# board.net
KiCad netlist of a schematic drawn in EAGLE
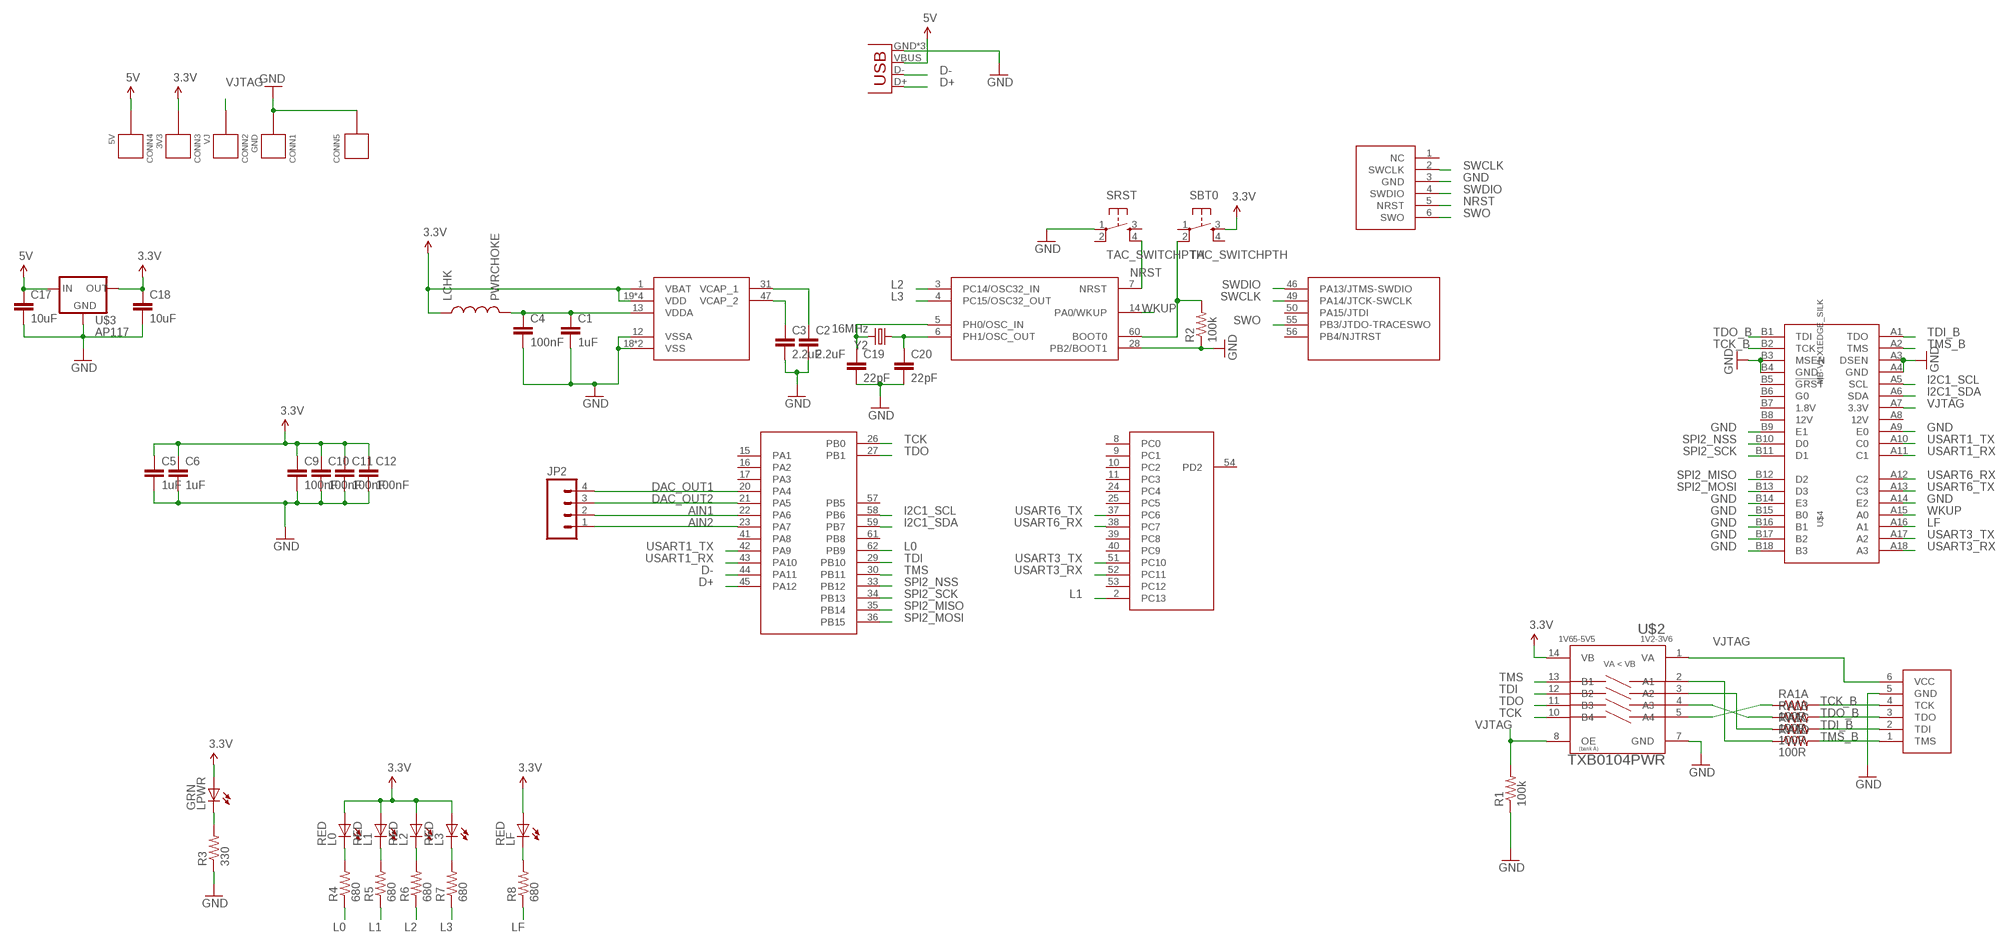
[diagram p0: schematic, sheet 1]

(export (version "E")
  (design (tool "Eeschema 10.0.6"))
  (components
    (comp (ref "C1")
      (value "1uF")
      (footprint "eagle-import:0603-CAP")
      (libsource (lib "eagle-import") (part "CAP0603"))
    )
    (comp (ref "C2")
      (value "2.2uF")
      (footprint "eagle-import:0603-CAP")
      (libsource (lib "eagle-import") (part "CAP0603"))
    )
    (comp (ref "C3")
      (value "2.2uF")
      (footprint "eagle-import:0603-CAP")
      (libsource (lib "eagle-import") (part "CAP0603"))
    )
    (comp (ref "C4")
      (value "100nF")
      (footprint "eagle-import:0402-CAP")
      (libsource (lib "eagle-import") (part "CAP0402-CAP"))
    )
    (comp (ref "C5")
      (value "1uF")
      (footprint "eagle-import:0603-CAP")
      (libsource (lib "eagle-import") (part "CAP0603"))
    )
    (comp (ref "C6")
      (value "1uF")
      (footprint "eagle-import:0603-CAP")
      (libsource (lib "eagle-import") (part "CAP0603"))
    )
    (comp (ref "C9")
      (value "100nF")
      (footprint "eagle-import:0402-CAP")
      (libsource (lib "eagle-import") (part "CAP0402-CAP"))
    )
    (comp (ref "C10")
      (value "100nF")
      (footprint "eagle-import:0402-CAP")
      (libsource (lib "eagle-import") (part "CAP0402-CAP"))
    )
    (comp (ref "C11")
      (value "100nF")
      (footprint "eagle-import:0402-CAP")
      (libsource (lib "eagle-import") (part "CAP0402-CAP"))
    )
    (comp (ref "C12")
      (value "100nF")
      (footprint "eagle-import:0402-CAP")
      (libsource (lib "eagle-import") (part "CAP0402-CAP"))
    )
    (comp (ref "C17")
      (value "10uF")
      (footprint "eagle-import:0805")
      (libsource (lib "eagle-import") (part "CAP0805"))
    )
    (comp (ref "C18")
      (value "10uF")
      (footprint "eagle-import:0805")
      (libsource (lib "eagle-import") (part "CAP0805"))
    )
    (comp (ref "C19")
      (value "22pF")
      (footprint "eagle-import:0402-CAP")
      (libsource (lib "eagle-import") (part "CAP0402-CAP"))
    )
    (comp (ref "C20")
      (value "22pF")
      (footprint "eagle-import:0402-CAP")
      (libsource (lib "eagle-import") (part "CAP0402-CAP"))
    )
    (comp (ref "CONN1")
      (value "GND")
      (footprint "eagle-import:HOLE_22AWG")
      (libsource (lib "eagle-import") (part "CONNECTOR22AWG"))
    )
    (comp (ref "CONN2")
      (value "VJ")
      (footprint "eagle-import:HOLE_22AWG")
      (libsource (lib "eagle-import") (part "CONNECTOR22AWG"))
    )
    (comp (ref "CONN3")
      (value "3V3")
      (footprint "eagle-import:HOLE_22AWG")
      (libsource (lib "eagle-import") (part "CONNECTOR22AWG"))
    )
    (comp (ref "CONN4")
      (value "5V")
      (footprint "eagle-import:HOLE_22AWG")
      (libsource (lib "eagle-import") (part "CONNECTOR22AWG"))
    )
    (comp (ref "CONN5")
      (value "CONNECTORCLIP")
      (footprint "eagle-import:CLIP-AREA")
      (libsource (lib "eagle-import") (part "CONNECTORCLIP"))
    )
    (comp (ref "JP1")
      (value "USB-MICROB")
      (footprint "eagle-import:USB-MICROB")
      (libsource (lib "eagle-import") (part "USB-MICROB"))
    )
    (comp (ref "JP2")
      (value "M04PTH")
      (footprint "eagle-import:1X04")
      (libsource (lib "eagle-import") (part "M04PTH"))
    )
    (comp (ref "L0")
      (value "RED")
      (footprint "eagle-import:0603_LED")
      (libsource (lib "eagle-import") (part "LED0603"))
    )
    (comp (ref "L1")
      (value "RED")
      (footprint "eagle-import:0603_LED")
      (libsource (lib "eagle-import") (part "LED0603"))
    )
    (comp (ref "L2")
      (value "RED")
      (footprint "eagle-import:0603_LED")
      (libsource (lib "eagle-import") (part "LED0603"))
    )
    (comp (ref "L3")
      (value "RED")
      (footprint "eagle-import:0603_LED")
      (libsource (lib "eagle-import") (part "LED0603"))
    )
    (comp (ref "LCHK")
      (value "PWRCHOKE")
      (footprint "eagle-import:0603")
      (libsource (lib "eagle-import") (part "INDUCTOR0603"))
    )
    (comp (ref "LF")
      (value "RED")
      (footprint "eagle-import:0603_LED")
      (libsource (lib "eagle-import") (part "LED0603"))
    )
    (comp (ref "LPWR")
      (value "GRN")
      (footprint "eagle-import:0603_LED")
      (libsource (lib "eagle-import") (part "LED0603"))
    )
    (comp (ref "R1")
      (value "100k")
      (footprint "eagle-import:0603-RES")
      (libsource (lib "eagle-import") (part "RESISTOR0603"))
    )
    (comp (ref "R2")
      (value "100k")
      (footprint "eagle-import:0603-RES")
      (libsource (lib "eagle-import") (part "RESISTOR0603"))
    )
    (comp (ref "R3")
      (value "330")
      (footprint "eagle-import:0603-RES")
      (libsource (lib "eagle-import") (part "RESISTOR0603"))
    )
    (comp (ref "R4")
      (value "680")
      (footprint "eagle-import:0603-RES")
      (libsource (lib "eagle-import") (part "RESISTOR0603"))
    )
    (comp (ref "R5")
      (value "680")
      (footprint "eagle-import:0603-RES")
      (libsource (lib "eagle-import") (part "RESISTOR0603"))
    )
    (comp (ref "R6")
      (value "680")
      (footprint "eagle-import:0603-RES")
      (libsource (lib "eagle-import") (part "RESISTOR0603"))
    )
    (comp (ref "R7")
      (value "680")
      (footprint "eagle-import:0603-RES")
      (libsource (lib "eagle-import") (part "RESISTOR0603"))
    )
    (comp (ref "R8")
      (value "680")
      (footprint "eagle-import:0603-RES")
      (libsource (lib "eagle-import") (part "RESISTOR0603"))
    )
    (comp (ref "RA1")
      (value "100R")
      (footprint "eagle-import:0603-ARV")
      (libsource (lib "eagle-import") (part "RESISTOR_ARRAY0603_X4"))
    )
    (comp (ref "SBT0")
      (value "TAC_SWITCHPTH")
      (footprint "eagle-import:TACTILE-PTH")
      (libsource (lib "eagle-import") (part "TAC_SWITCHPTH"))
    )
    (comp (ref "SRST")
      (value "TAC_SWITCHPTH")
      (footprint "eagle-import:TACTILE-PTH")
      (libsource (lib "eagle-import") (part "TAC_SWITCHPTH"))
    )
    (comp (ref "U$1")
      (value "STM32F407R")
      (footprint "eagle-import:TQFP64_LONGPAD")
      (libsource (lib "eagle-import") (part "STM32F407R"))
    )
    (comp (ref "U$2")
      (value "TXB0104PWR")
      (footprint "eagle-import:TSSOP14")
      (libsource (lib "eagle-import") (part "TXB0104PWR"))
    )
    (comp (ref "U$3")
      (value "AP117")
      (footprint "eagle-import:SOT223")
      (libsource (lib "eagle-import") (part "VREGSOT223"))
    )
    (comp (ref "U$4")
      (value "MB-V1-X1EDGE_SILK")
      (footprint "eagle-import:MB-V1-X1-EDGE")
      (libsource (lib "eagle-import") (part "MB-V1-X1EDGE_SILK"))
    )
    (comp (ref "U$5")
      (value "JTAGDIGILENT")
      (footprint "eagle-import:1X06")
      (libsource (lib "eagle-import") (part "JTAGDIGILENT"))
    )
    (comp (ref "U$6")
      (value "STLINK")
      (footprint "eagle-import:1X06")
      (libsource (lib "eagle-import") (part "STLINK"))
    )
    (comp (ref "Y2")
      (value "16MHz")
      (footprint "eagle-import:HC49US")
      (libsource (lib "eagle-import") (part "CRYSTALHC49US"))
    )
  )
  (nets
    (net (code "1") (name "/AIN1") (class "Default")
      (node (ref "JP2") (pin "2") (pinfunction "2_2") (pintype "passive"))
      (node (ref "U$1") (pin "22") (pinfunction "PA6_22") (pintype "bidirectional"))
    )
    (net (code "2") (name "/AIN2") (class "Default")
      (node (ref "JP2") (pin "1") (pinfunction "1_1") (pintype "passive"))
      (node (ref "U$1") (pin "23") (pinfunction "PA7_23") (pintype "bidirectional"))
    )
    (net (code "3") (name "/D+") (class "Default")
      (node (ref "JP1") (pin "D+") (pinfunction "D+_D+") (pintype "bidirectional"))
      (node (ref "U$1") (pin "45") (pinfunction "PA12_45") (pintype "bidirectional"))
    )
    (net (code "4") (name "/D-") (class "Default")
      (node (ref "JP1") (pin "D-") (pinfunction "D-_D-") (pintype "bidirectional"))
      (node (ref "U$1") (pin "44") (pinfunction "PA11_44") (pintype "bidirectional"))
    )
    (net (code "5") (name "/DAC_OUT1") (class "Default")
      (node (ref "JP2") (pin "4") (pinfunction "4_4") (pintype "passive"))
      (node (ref "U$1") (pin "20") (pinfunction "PA4_20") (pintype "bidirectional"))
    )
    (net (code "6") (name "/DAC_OUT2") (class "Default")
      (node (ref "JP2") (pin "3") (pinfunction "3_3") (pintype "passive"))
      (node (ref "U$1") (pin "21") (pinfunction "PA5_21") (pintype "bidirectional"))
    )
    (net (code "7") (name "/I2C1_SCL") (class "Default")
      (node (ref "U$1") (pin "58") (pinfunction "PB6_58") (pintype "bidirectional"))
      (node (ref "U$4") (pin "A5") (pinfunction "SCL_A5") (pintype "bidirectional"))
    )
    (net (code "8") (name "/I2C1_SDA") (class "Default")
      (node (ref "U$1") (pin "59") (pinfunction "PB7_59") (pintype "bidirectional"))
      (node (ref "U$4") (pin "A6") (pinfunction "SDA_A6") (pintype "bidirectional"))
    )
    (net (code "9") (name "/L0") (class "Default")
      (node (ref "R4") (pin "1") (pinfunction "1_1") (pintype "passive"))
      (node (ref "U$1") (pin "62") (pinfunction "PB9_62") (pintype "bidirectional"))
    )
    (net (code "10") (name "/L1") (class "Default")
      (node (ref "R5") (pin "1") (pinfunction "1_1") (pintype "passive"))
      (node (ref "U$1") (pin "2") (pinfunction "PC13_2") (pintype "bidirectional"))
    )
    (net (code "11") (name "/L2") (class "Default")
      (node (ref "R6") (pin "1") (pinfunction "1_1") (pintype "passive"))
      (node (ref "U$1") (pin "3") (pinfunction "PC14/OSC32_IN_3") (pintype "bidirectional"))
    )
    (net (code "12") (name "/L3") (class "Default")
      (node (ref "R7") (pin "1") (pinfunction "1_1") (pintype "passive"))
      (node (ref "U$1") (pin "4") (pinfunction "PC15/OSC32_OUT_4") (pintype "bidirectional"))
    )
    (net (code "13") (name "/LF") (class "Default")
      (node (ref "R8") (pin "1") (pinfunction "1_1") (pintype "passive"))
      (node (ref "U$4") (pin "A16") (pinfunction "A1_A16") (pintype "bidirectional"))
    )
    (net (code "14") (name "/NRST") (class "Default")
      (node (ref "SRST") (pin "4") (pinfunction "4_4") (pintype "passive"))
      (node (ref "U$1") (pin "7") (pinfunction "NRST_7") (pintype "input"))
      (node (ref "U$6") (pin "5") (pinfunction "NRST_5") (pintype "bidirectional"))
    )
    (net (code "15") (name "/SPI2_MISO") (class "Default")
      (node (ref "U$1") (pin "35") (pinfunction "PB14_35") (pintype "bidirectional"))
      (node (ref "U$4") (pin "B12") (pinfunction "D2_B12") (pintype "bidirectional"))
    )
    (net (code "16") (name "/SPI2_MOSI") (class "Default")
      (node (ref "U$1") (pin "36") (pinfunction "PB15_36") (pintype "bidirectional"))
      (node (ref "U$4") (pin "B13") (pinfunction "D3_B13") (pintype "bidirectional"))
    )
    (net (code "17") (name "/SPI2_NSS") (class "Default")
      (node (ref "U$1") (pin "33") (pinfunction "PB12_33") (pintype "bidirectional"))
      (node (ref "U$4") (pin "B10") (pinfunction "D0_B10") (pintype "bidirectional"))
    )
    (net (code "18") (name "/SPI2_SCK") (class "Default")
      (node (ref "U$1") (pin "34") (pinfunction "PB13_34") (pintype "bidirectional"))
      (node (ref "U$4") (pin "B11") (pinfunction "D1_B11") (pintype "bidirectional"))
    )
    (net (code "19") (name "/SWCLK") (class "Default")
      (node (ref "U$1") (pin "49") (pinfunction "PA14/JTCK-SWCLK_49") (pintype "bidirectional"))
      (node (ref "U$6") (pin "2") (pinfunction "SWCLK_2") (pintype "bidirectional"))
    )
    (net (code "20") (name "/SWDIO") (class "Default")
      (node (ref "U$1") (pin "46") (pinfunction "PA13/JTMS-SWDIO_46") (pintype "bidirectional"))
      (node (ref "U$6") (pin "4") (pinfunction "SWDIO_4") (pintype "bidirectional"))
    )
    (net (code "21") (name "/SWO") (class "Default")
      (node (ref "U$1") (pin "55") (pinfunction "PB3/JTDO-TRACESWO_55") (pintype "bidirectional"))
      (node (ref "U$6") (pin "6") (pinfunction "SWO_6") (pintype "bidirectional"))
    )
    (net (code "22") (name "/TCK") (class "Default")
      (node (ref "U$1") (pin "26") (pinfunction "PB0_26") (pintype "bidirectional"))
      (node (ref "U$2") (pin "10") (pinfunction "B4_10") (pintype "bidirectional"))
    )
    (net (code "23") (name "/TCK_B") (class "Default")
      (node (ref "RA1") (pin "8") (pinfunction "2_8") (pintype "passive"))
      (node (ref "U$4") (pin "B2") (pinfunction "TCK_B2") (pintype "bidirectional"))
      (node (ref "U$5") (pin "4") (pinfunction "TCK_4") (pintype "bidirectional"))
    )
    (net (code "24") (name "/TDI") (class "Default")
      (node (ref "U$1") (pin "29") (pinfunction "PB10_29") (pintype "bidirectional"))
      (node (ref "U$2") (pin "12") (pinfunction "B2_12") (pintype "bidirectional"))
    )
    (net (code "25") (name "/TDI_B") (class "Default")
      (node (ref "RA1") (pin "6") (pinfunction "2_6") (pintype "passive"))
      (node (ref "U$4") (pin "A1") (pinfunction "TDO_A1") (pintype "bidirectional"))
      (node (ref "U$5") (pin "2") (pinfunction "TDI_2") (pintype "bidirectional"))
    )
    (net (code "26") (name "/TDO") (class "Default")
      (node (ref "U$1") (pin "27") (pinfunction "PB1_27") (pintype "bidirectional"))
      (node (ref "U$2") (pin "11") (pinfunction "B3_11") (pintype "bidirectional"))
    )
    (net (code "27") (name "/TDO_B") (class "Default")
      (node (ref "RA1") (pin "7") (pinfunction "2_7") (pintype "passive"))
      (node (ref "U$4") (pin "B1") (pinfunction "TDI_B1") (pintype "bidirectional"))
      (node (ref "U$5") (pin "3") (pinfunction "TDO_3") (pintype "bidirectional"))
    )
    (net (code "28") (name "/TMS") (class "Default")
      (node (ref "U$1") (pin "30") (pinfunction "PB11_30") (pintype "bidirectional"))
      (node (ref "U$2") (pin "13") (pinfunction "B1_13") (pintype "bidirectional"))
    )
    (net (code "29") (name "/TMS_B") (class "Default")
      (node (ref "RA1") (pin "5") (pinfunction "2_5") (pintype "passive"))
      (node (ref "U$4") (pin "A2") (pinfunction "TMS_A2") (pintype "bidirectional"))
      (node (ref "U$5") (pin "1") (pinfunction "TMS_1") (pintype "bidirectional"))
    )
    (net (code "30") (name "/USART1_RX") (class "Default")
      (node (ref "U$1") (pin "43") (pinfunction "PA10_43") (pintype "bidirectional"))
      (node (ref "U$4") (pin "A11") (pinfunction "C1_A11") (pintype "bidirectional"))
    )
    (net (code "31") (name "/USART1_TX") (class "Default")
      (node (ref "U$1") (pin "42") (pinfunction "PA9_42") (pintype "bidirectional"))
      (node (ref "U$4") (pin "A10") (pinfunction "C0_A10") (pintype "bidirectional"))
    )
    (net (code "32") (name "/USART3_RX") (class "Default")
      (node (ref "U$1") (pin "52") (pinfunction "PC11_52") (pintype "bidirectional"))
      (node (ref "U$4") (pin "A18") (pinfunction "A3_A18") (pintype "bidirectional"))
    )
    (net (code "33") (name "/USART3_TX") (class "Default")
      (node (ref "U$1") (pin "51") (pinfunction "PC10_51") (pintype "bidirectional"))
      (node (ref "U$4") (pin "A17") (pinfunction "A2_A17") (pintype "bidirectional"))
    )
    (net (code "34") (name "/USART6_RX") (class "Default")
      (node (ref "U$1") (pin "38") (pinfunction "PC7_38") (pintype "bidirectional"))
      (node (ref "U$4") (pin "A12") (pinfunction "C2_A12") (pintype "bidirectional"))
    )
    (net (code "35") (name "/USART6_TX") (class "Default")
      (node (ref "U$1") (pin "37") (pinfunction "PC6_37") (pintype "bidirectional"))
      (node (ref "U$4") (pin "A13") (pinfunction "C3_A13") (pintype "bidirectional"))
    )
    (net (code "36") (name "/VJTAG") (class "Default")
      (node (ref "CONN2") (pin "P") (pinfunction "P_P") (pintype "bidirectional"))
      (node (ref "R1") (pin "2") (pinfunction "2_2") (pintype "passive"))
      (node (ref "U$2") (pin "1") (pinfunction "VA_1") (pintype "bidirectional"))
      (node (ref "U$2") (pin "8") (pinfunction "OE_8") (pintype "bidirectional"))
      (node (ref "U$4") (pin "A7") (pinfunction "3.3V_A7") (pintype "bidirectional"))
      (node (ref "U$5") (pin "6") (pinfunction "VCC_6") (pintype "bidirectional"))
    )
    (net (code "37") (name "/WKUP") (class "Default")
      (node (ref "U$1") (pin "14") (pinfunction "PA0/WKUP_14") (pintype "input"))
      (node (ref "U$4") (pin "A15") (pinfunction "A0_A15") (pintype "bidirectional"))
    )
    (net (code "38") (name "3.3V") (class "Default")
      (node (ref "C10") (pin "1") (pinfunction "1_1") (pintype "passive"))
      (node (ref "C11") (pin "1") (pinfunction "1_1") (pintype "passive"))
      (node (ref "C12") (pin "1") (pinfunction "1_1") (pintype "passive"))
      (node (ref "C18") (pin "1") (pinfunction "1_1") (pintype "passive"))
      (node (ref "C5") (pin "1") (pinfunction "1_1") (pintype "passive"))
      (node (ref "C6") (pin "1") (pinfunction "1_1") (pintype "passive"))
      (node (ref "C9") (pin "1") (pinfunction "1_1") (pintype "passive"))
      (node (ref "CONN3") (pin "P") (pinfunction "P_P") (pintype "bidirectional"))
      (node (ref "L0") (pin "A") (pinfunction "A_A") (pintype "passive"))
      (node (ref "L1") (pin "A") (pinfunction "A_A") (pintype "passive"))
      (node (ref "L2") (pin "A") (pinfunction "A_A") (pintype "passive"))
      (node (ref "L3") (pin "A") (pinfunction "A_A") (pintype "passive"))
      (node (ref "LCHK") (pin "1") (pinfunction "1_1") (pintype "passive"))
      (node (ref "LF") (pin "A") (pinfunction "A_A") (pintype "passive"))
      (node (ref "LPWR") (pin "A") (pinfunction "A_A") (pintype "passive"))
      (node (ref "SBT0") (pin "3") (pinfunction "3_3") (pintype "passive"))
      (node (ref "U$1") (pin "1") (pinfunction "VBAT_1") (pintype "input"))
      (node (ref "U$1") (pin "19") (pinfunction "VDD_19") (pintype "input"))
      (node (ref "U$1") (pin "32") (pinfunction "VDD_32") (pintype "input"))
      (node (ref "U$1") (pin "48") (pinfunction "VDD_48") (pintype "input"))
      (node (ref "U$1") (pin "64") (pinfunction "VDD_64") (pintype "input"))
      (node (ref "U$2") (pin "14") (pinfunction "VB_14") (pintype "bidirectional"))
      (node (ref "U$3") (pin "2") (pinfunction "OUT_2") (pintype "passive"))
      (node (ref "U$3") (pin "4") (pinfunction "OUT_4") (pintype "passive"))
    )
    (net (code "39") (name "5V") (class "Default")
      (node (ref "C17") (pin "1") (pinfunction "1_1") (pintype "passive"))
      (node (ref "CONN4") (pin "P") (pinfunction "P_P") (pintype "bidirectional"))
      (node (ref "JP1") (pin "VBUS") (pinfunction "VBUS_VBUS") (pintype "bidirectional"))
      (node (ref "U$3") (pin "3") (pinfunction "IN_3") (pintype "input"))
    )
    (net (code "40") (name "GND") (class "Default")
      (node (ref "C1") (pin "2") (pinfunction "2_2") (pintype "passive"))
      (node (ref "C10") (pin "2") (pinfunction "2_2") (pintype "passive"))
      (node (ref "C11") (pin "2") (pinfunction "2_2") (pintype "passive"))
      (node (ref "C12") (pin "2") (pinfunction "2_2") (pintype "passive"))
      (node (ref "C17") (pin "2") (pinfunction "2_2") (pintype "passive"))
      (node (ref "C18") (pin "2") (pinfunction "2_2") (pintype "passive"))
      (node (ref "C19") (pin "2") (pinfunction "2_2") (pintype "passive"))
      (node (ref "C2") (pin "2") (pinfunction "2_2") (pintype "passive"))
      (node (ref "C20") (pin "2") (pinfunction "2_2") (pintype "passive"))
      (node (ref "C3") (pin "2") (pinfunction "2_2") (pintype "passive"))
      (node (ref "C4") (pin "2") (pinfunction "2_2") (pintype "passive"))
      (node (ref "C5") (pin "2") (pinfunction "2_2") (pintype "passive"))
      (node (ref "C6") (pin "2") (pinfunction "2_2") (pintype "passive"))
      (node (ref "C9") (pin "2") (pinfunction "2_2") (pintype "passive"))
      (node (ref "CONN1") (pin "P") (pinfunction "P_P") (pintype "bidirectional"))
      (node (ref "CONN5") (pin "P$1") (pinfunction "P_P$1") (pintype "bidirectional"))
      (node (ref "CONN5") (pin "P$2") (pinfunction "P_P$2") (pintype "bidirectional"))
      (node (ref "JP1") (pin "GND") (pinfunction "GND_GND") (pintype "bidirectional"))
      (node (ref "JP1") (pin "MT1") (pinfunction "GND_MT1") (pintype "bidirectional"))
      (node (ref "JP1") (pin "MT2") (pinfunction "GND_MT2") (pintype "bidirectional"))
      (node (ref "R1") (pin "1") (pinfunction "1_1") (pintype "passive"))
      (node (ref "R2") (pin "1") (pinfunction "1_1") (pintype "passive"))
      (node (ref "R3") (pin "1") (pinfunction "1_1") (pintype "passive"))
      (node (ref "SRST") (pin "1") (pinfunction "1_1") (pintype "passive"))
      (node (ref "U$1") (pin "12") (pinfunction "VSSA_12") (pintype "input"))
      (node (ref "U$1") (pin "18") (pinfunction "VSS_18") (pintype "input"))
      (node (ref "U$1") (pin "28") (pinfunction "PB2/BOOT1_28") (pintype "input"))
      (node (ref "U$1") (pin "63") (pinfunction "VSS_63") (pintype "input"))
      (node (ref "U$2") (pin "7") (pinfunction "GND_7") (pintype "bidirectional"))
      (node (ref "U$3") (pin "1") (pinfunction "GND_1") (pintype "input"))
      (node (ref "U$4") (pin "A14") (pinfunction "E2_A14") (pintype "bidirectional"))
      (node (ref "U$4") (pin "A3") (pinfunction "DSEN_A3") (pintype "bidirectional"))
      (node (ref "U$4") (pin "A4") (pinfunction "GND_A4") (pintype "bidirectional"))
      (node (ref "U$4") (pin "A9") (pinfunction "E0_A9") (pintype "bidirectional"))
      (node (ref "U$4") (pin "B14") (pinfunction "E3_B14") (pintype "bidirectional"))
      (node (ref "U$4") (pin "B15") (pinfunction "B0_B15") (pintype "bidirectional"))
      (node (ref "U$4") (pin "B16") (pinfunction "B1_B16") (pintype "bidirectional"))
      (node (ref "U$4") (pin "B17") (pinfunction "B2_B17") (pintype "bidirectional"))
      (node (ref "U$4") (pin "B18") (pinfunction "B3_B18") (pintype "bidirectional"))
      (node (ref "U$4") (pin "B3") (pinfunction "MSEN_B3") (pintype "bidirectional"))
      (node (ref "U$4") (pin "B4") (pinfunction "GND_B4") (pintype "bidirectional"))
      (node (ref "U$4") (pin "B9") (pinfunction "E1_B9") (pintype "bidirectional"))
      (node (ref "U$5") (pin "5") (pinfunction "GND_5") (pintype "bidirectional"))
      (node (ref "U$6") (pin "3") (pinfunction "GND_3") (pintype "bidirectional"))
    )
    (net (code "41") (name "Net-(L0-PadC)") (class "Default")
      (node (ref "L0") (pin "C") (pinfunction "C_C") (pintype "passive"))
      (node (ref "R4") (pin "2") (pinfunction "2_2") (pintype "passive"))
    )
    (net (code "42") (name "Net-(L1-PadC)") (class "Default")
      (node (ref "L1") (pin "C") (pinfunction "C_C") (pintype "passive"))
      (node (ref "R5") (pin "2") (pinfunction "2_2") (pintype "passive"))
    )
    (net (code "43") (name "Net-(L2-PadC)") (class "Default")
      (node (ref "L2") (pin "C") (pinfunction "C_C") (pintype "passive"))
      (node (ref "R6") (pin "2") (pinfunction "2_2") (pintype "passive"))
    )
    (net (code "44") (name "Net-(L3-PadC)") (class "Default")
      (node (ref "L3") (pin "C") (pinfunction "C_C") (pintype "passive"))
      (node (ref "R7") (pin "2") (pinfunction "2_2") (pintype "passive"))
    )
    (net (code "45") (name "Net-(LF-PadC)") (class "Default")
      (node (ref "LF") (pin "C") (pinfunction "C_C") (pintype "passive"))
      (node (ref "R8") (pin "2") (pinfunction "2_2") (pintype "passive"))
    )
    (net (code "46") (name "Net-(LPWR-PadC)") (class "Default")
      (node (ref "LPWR") (pin "C") (pinfunction "C_C") (pintype "passive"))
      (node (ref "R3") (pin "2") (pinfunction "2_2") (pintype "passive"))
    )
    (net (code "47") (name "Net-(RA1B-1)") (class "Default")
      (node (ref "RA1") (pin "2") (pinfunction "1_2") (pintype "passive"))
      (node (ref "U$2") (pin "4") (pinfunction "A3_4") (pintype "bidirectional"))
    )
    (net (code "48") (name "Net-(RA1C-1)") (class "Default")
      (node (ref "RA1") (pin "3") (pinfunction "1_3") (pintype "passive"))
      (node (ref "U$2") (pin "3") (pinfunction "A2_3") (pintype "bidirectional"))
    )
    (net (code "49") (name "Net-(RA1D-1)") (class "Default")
      (node (ref "RA1") (pin "4") (pinfunction "1_4") (pintype "passive"))
      (node (ref "U$2") (pin "2") (pinfunction "A1_2") (pintype "bidirectional"))
    )
    (net (code "50") (name "Net-(U$1-BOOT0)") (class "Default")
      (node (ref "R2") (pin "2") (pinfunction "2_2") (pintype "passive"))
      (node (ref "SBT0") (pin "2") (pinfunction "2_2") (pintype "passive"))
      (node (ref "U$1") (pin "60") (pinfunction "BOOT0_60") (pintype "input"))
    )
    (net (code "51") (name "Net-(U$1-PH0{slash}OSC_IN)") (class "Default")
      (node (ref "C19") (pin "1") (pinfunction "1_1") (pintype "passive"))
      (node (ref "U$1") (pin "5") (pinfunction "PH0/OSC_IN_5") (pintype "bidirectional"))
      (node (ref "Y2") (pin "2") (pinfunction "2_2") (pintype "passive"))
    )
    (net (code "52") (name "Net-(U$1-PH1{slash}OSC_OUT)") (class "Default")
      (node (ref "C20") (pin "1") (pinfunction "1_1") (pintype "passive"))
      (node (ref "U$1") (pin "6") (pinfunction "PH1/OSC_OUT_6") (pintype "bidirectional"))
      (node (ref "Y2") (pin "1") (pinfunction "1_1") (pintype "passive"))
    )
    (net (code "53") (name "Net-(U$1-VCAP_1)") (class "Default")
      (node (ref "C2") (pin "1") (pinfunction "1_1") (pintype "passive"))
      (node (ref "U$1") (pin "31") (pinfunction "VCAP_1_31") (pintype "input"))
    )
    (net (code "54") (name "Net-(U$1-VCAP_2)") (class "Default")
      (node (ref "C3") (pin "1") (pinfunction "1_1") (pintype "passive"))
      (node (ref "U$1") (pin "47") (pinfunction "VCAP_2_47") (pintype "input"))
    )
    (net (code "55") (name "Net-(U$1-VDDA)") (class "Default")
      (node (ref "C1") (pin "1") (pinfunction "1_1") (pintype "passive"))
      (node (ref "C4") (pin "1") (pinfunction "1_1") (pintype "passive"))
      (node (ref "LCHK") (pin "2") (pinfunction "2_2") (pintype "passive"))
      (node (ref "U$1") (pin "13") (pinfunction "VDDA_13") (pintype "input"))
    )
    (net (code "56") (name "Net-(U$2-A4)") (class "Default")
      (node (ref "RA1") (pin "1") (pinfunction "1_1") (pintype "passive"))
      (node (ref "U$2") (pin "5") (pinfunction "A4_5") (pintype "bidirectional"))
    )
    (net (code "57") (name "unconnected-(SBT0-Pad1)") (class "Default")
      (node (ref "SBT0") (pin "1") (pinfunction "1_1") (pintype "passive"))
    )
    (net (code "58") (name "unconnected-(SBT0-Pad4)") (class "Default")
      (node (ref "SBT0") (pin "4") (pinfunction "4_4") (pintype "passive"))
    )
    (net (code "59") (name "unconnected-(SRST-Pad2)") (class "Default")
      (node (ref "SRST") (pin "2") (pinfunction "2_2") (pintype "passive"))
    )
    (net (code "60") (name "unconnected-(SRST-Pad3)") (class "Default")
      (node (ref "SRST") (pin "3") (pinfunction "3_3") (pintype "passive"))
    )
    (net (code "61") (name "unconnected-(U$1-PA1-Pad15)") (class "Default")
      (node (ref "U$1") (pin "15") (pinfunction "PA1_15") (pintype "bidirectional"))
    )
    (net (code "62") (name "unconnected-(U$1-PA2-Pad16)") (class "Default")
      (node (ref "U$1") (pin "16") (pinfunction "PA2_16") (pintype "bidirectional"))
    )
    (net (code "63") (name "unconnected-(U$1-PA3-Pad17)") (class "Default")
      (node (ref "U$1") (pin "17") (pinfunction "PA3_17") (pintype "bidirectional"))
    )
    (net (code "64") (name "unconnected-(U$1-PA8-Pad41)") (class "Default")
      (node (ref "U$1") (pin "41") (pinfunction "PA8_41") (pintype "bidirectional"))
    )
    (net (code "65") (name "unconnected-(U$1-PA15{slash}JTDI-Pad50)") (class "Default")
      (node (ref "U$1") (pin "50") (pinfunction "PA15/JTDI_50") (pintype "bidirectional"))
    )
    (net (code "66") (name "unconnected-(U$1-PB4{slash}NJTRST-Pad56)") (class "Default")
      (node (ref "U$1") (pin "56") (pinfunction "PB4/NJTRST_56") (pintype "bidirectional"))
    )
    (net (code "67") (name "unconnected-(U$1-PB5-Pad57)") (class "Default")
      (node (ref "U$1") (pin "57") (pinfunction "PB5_57") (pintype "bidirectional"))
    )
    (net (code "68") (name "unconnected-(U$1-PB8-Pad61)") (class "Default")
      (node (ref "U$1") (pin "61") (pinfunction "PB8_61") (pintype "bidirectional"))
    )
    (net (code "69") (name "unconnected-(U$1-PC0-Pad8)") (class "Default")
      (node (ref "U$1") (pin "8") (pinfunction "PC0_8") (pintype "bidirectional"))
    )
    (net (code "70") (name "unconnected-(U$1-PC1-Pad9)") (class "Default")
      (node (ref "U$1") (pin "9") (pinfunction "PC1_9") (pintype "bidirectional"))
    )
    (net (code "71") (name "unconnected-(U$1-PC2-Pad10)") (class "Default")
      (node (ref "U$1") (pin "10") (pinfunction "PC2_10") (pintype "bidirectional"))
    )
    (net (code "72") (name "unconnected-(U$1-PC3-Pad11)") (class "Default")
      (node (ref "U$1") (pin "11") (pinfunction "PC3_11") (pintype "bidirectional"))
    )
    (net (code "73") (name "unconnected-(U$1-PC4-Pad24)") (class "Default")
      (node (ref "U$1") (pin "24") (pinfunction "PC4_24") (pintype "bidirectional"))
    )
    (net (code "74") (name "unconnected-(U$1-PC5-Pad25)") (class "Default")
      (node (ref "U$1") (pin "25") (pinfunction "PC5_25") (pintype "bidirectional"))
    )
    (net (code "75") (name "unconnected-(U$1-PC8-Pad39)") (class "Default")
      (node (ref "U$1") (pin "39") (pinfunction "PC8_39") (pintype "bidirectional"))
    )
    (net (code "76") (name "unconnected-(U$1-PC9-Pad40)") (class "Default")
      (node (ref "U$1") (pin "40") (pinfunction "PC9_40") (pintype "bidirectional"))
    )
    (net (code "77") (name "unconnected-(U$1-PC12-Pad53)") (class "Default")
      (node (ref "U$1") (pin "53") (pinfunction "PC12_53") (pintype "bidirectional"))
    )
    (net (code "78") (name "unconnected-(U$1-PD2-Pad54)") (class "Default")
      (node (ref "U$1") (pin "54") (pinfunction "PD2_54") (pintype "bidirectional"))
    )
    (net (code "79") (name "unconnected-(U$4-1.8V-PadB7)") (class "Default")
      (node (ref "U$4") (pin "B7") (pinfunction "1.8V_B7") (pintype "bidirectional"))
    )
    (net (code "80") (name "unconnected-(U$4-12V-PadA8)") (class "Default")
      (node (ref "U$4") (pin "A8") (pinfunction "12V_A8") (pintype "bidirectional"))
    )
    (net (code "81") (name "unconnected-(U$4-12V-PadB8)") (class "Default")
      (node (ref "U$4") (pin "B8") (pinfunction "12V_B8") (pintype "bidirectional"))
    )
    (net (code "82") (name "unconnected-(U$4-G0-PadB6)") (class "Default")
      (node (ref "U$4") (pin "B6") (pinfunction "G0_B6") (pintype "bidirectional"))
    )
    (net (code "83") (name "unconnected-(U$4-~{GRST}-PadB5)") (class "Default")
      (node (ref "U$4") (pin "B5") (pinfunction "~{GRST}_B5") (pintype "bidirectional"))
    )
    (net (code "84") (name "unconnected-(U$6-NC-Pad1)") (class "Default")
      (node (ref "U$6") (pin "1") (pinfunction "NC_1") (pintype "bidirectional"))
    )
  )
)
